# SWG_1_1.net
KiCad netlist of a schematic drawn in EAGLE
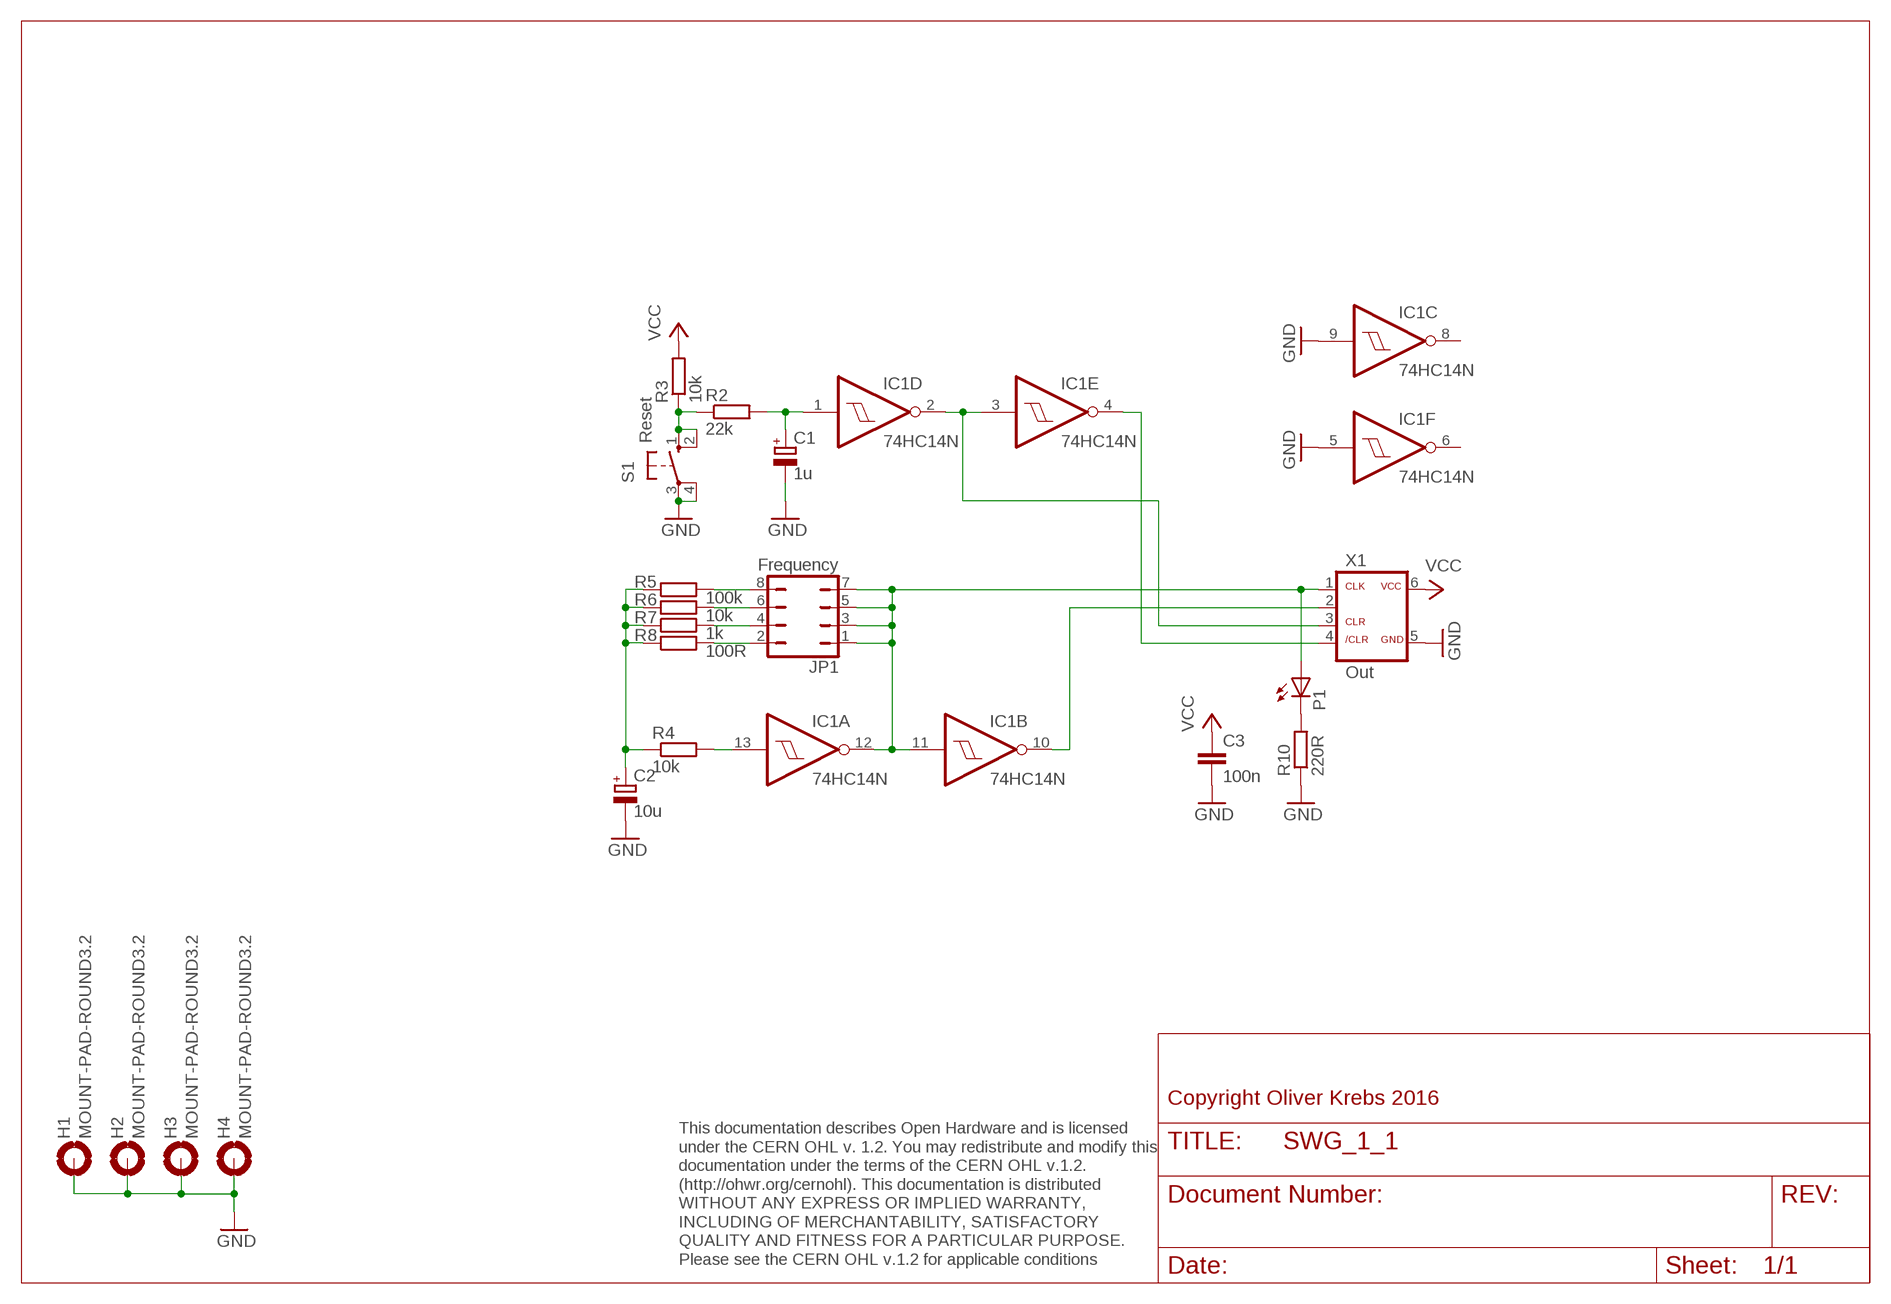
[diagram p0: schematic, sheet 1]

(export (version "E")
  (design (tool "Eeschema 10.0.6"))
  (components
    (comp (ref "C1")
      (value "1u")
      (footprint "eagle-import:E2-5")
      (libsource (lib "eagle-import") (part "CPOL-EUE2-5"))
    )
    (comp (ref "C2")
      (value "10u")
      (footprint "eagle-import:E2-5")
      (libsource (lib "eagle-import") (part "CPOL-EUE2-5"))
    )
    (comp (ref "C3")
      (value "100n")
      (footprint "eagle-import:C050-025X075")
      (libsource (lib "eagle-import") (part "C-EU050-025X075"))
    )
    (comp (ref "H1")
      (value "MOUNT-PAD-ROUND3.2")
      (footprint "eagle-import:3,2-PAD")
      (libsource (lib "eagle-import") (part "MOUNT-PAD-ROUND3.2"))
    )
    (comp (ref "H2")
      (value "MOUNT-PAD-ROUND3.2")
      (footprint "eagle-import:3,2-PAD")
      (libsource (lib "eagle-import") (part "MOUNT-PAD-ROUND3.2"))
    )
    (comp (ref "H3")
      (value "MOUNT-PAD-ROUND3.2")
      (footprint "eagle-import:3,2-PAD")
      (libsource (lib "eagle-import") (part "MOUNT-PAD-ROUND3.2"))
    )
    (comp (ref "H4")
      (value "MOUNT-PAD-ROUND3.2")
      (footprint "eagle-import:3,2-PAD")
      (libsource (lib "eagle-import") (part "MOUNT-PAD-ROUND3.2"))
    )
    (comp (ref "IC1")
      (value "74HC14N")
      (footprint "eagle-import:DIL14")
      (libsource (lib "eagle-import") (part "7414NHC"))
    )
    (comp (ref "JP1")
      (value "Frequency")
      (footprint "eagle-import:JP4Q")
      (libsource (lib "eagle-import") (part "JP4Q"))
    )
    (comp (ref "P1")
      (value "LED3MM")
      (footprint "eagle-import:LED3MM")
      (libsource (lib "eagle-import") (part "LED3MM"))
    )
    (comp (ref "R2")
      (value "22k")
      (footprint "eagle-import:0207_10")
      (libsource (lib "eagle-import") (part "R-EU_0207/10"))
    )
    (comp (ref "R3")
      (value "10k")
      (footprint "eagle-import:0207_10")
      (libsource (lib "eagle-import") (part "R-EU_0207/10"))
    )
    (comp (ref "R4")
      (value "10k")
      (footprint "eagle-import:0207_10")
      (libsource (lib "eagle-import") (part "R-EU_0207/10"))
    )
    (comp (ref "R5")
      (value "100k")
      (footprint "eagle-import:0207_10")
      (libsource (lib "eagle-import") (part "R-EU_0207/10"))
    )
    (comp (ref "R6")
      (value "10k")
      (footprint "eagle-import:0207_10")
      (libsource (lib "eagle-import") (part "R-EU_0207/10"))
    )
    (comp (ref "R7")
      (value "1k")
      (footprint "eagle-import:0207_10")
      (libsource (lib "eagle-import") (part "R-EU_0207/10"))
    )
    (comp (ref "R8")
      (value "100R")
      (footprint "eagle-import:0207_10")
      (libsource (lib "eagle-import") (part "R-EU_0207/10"))
    )
    (comp (ref "R10")
      (value "220R")
      (footprint "eagle-import:0207_10")
      (libsource (lib "eagle-import") (part "R-EU_0207/10"))
    )
    (comp (ref "S1")
      (value "Reset")
      (footprint "eagle-import:B3F-10XX")
      (fields (field (name "MPN") "B3F-1000"))
      (libsource (lib "eagle-import") (part "10-XX"))
    )
    (comp (ref "X1")
      (value "Out")
      (footprint "eagle-import:ML-6")
      (libsource (lib "eagle-import") (part "ML6C"))
    )
  )
  (nets
    (net (code "1") (name "GND") (class "Default")
      (node (ref "C1") (pin "-") (pinfunction "-_-") (pintype "passive"))
      (node (ref "C2") (pin "-") (pinfunction "-_-") (pintype "passive"))
      (node (ref "C3") (pin "2") (pinfunction "2_2") (pintype "passive"))
      (node (ref "H1") (pin "B3,2") (pinfunction "MOUNT_B3,2") (pintype "passive"))
      (node (ref "H2") (pin "B3,2") (pinfunction "MOUNT_B3,2") (pintype "passive"))
      (node (ref "H3") (pin "B3,2") (pinfunction "MOUNT_B3,2") (pintype "passive"))
      (node (ref "H4") (pin "B3,2") (pinfunction "MOUNT_B3,2") (pintype "passive"))
      (node (ref "IC1") (pin "5") (pinfunction "I_5") (pintype "input"))
      (node (ref "IC1") (pin "9") (pinfunction "I_9") (pintype "input"))
      (node (ref "R10") (pin "1") (pinfunction "1_1") (pintype "passive"))
      (node (ref "S1") (pin "3") (pinfunction "P_3") (pintype "passive"))
      (node (ref "S1") (pin "4") (pinfunction "P1_4") (pintype "passive"))
      (node (ref "X1") (pin "5") (pinfunction "5_5") (pintype "passive"))
    )
    (net (code "2") (name "Net-(C2-Pad+)") (class "Default")
      (node (ref "C2") (pin "+") (pinfunction "+_+") (pintype "passive"))
      (node (ref "R4") (pin "1") (pinfunction "1_1") (pintype "passive"))
      (node (ref "R5") (pin "1") (pinfunction "1_1") (pintype "passive"))
      (node (ref "R6") (pin "1") (pinfunction "1_1") (pintype "passive"))
      (node (ref "R7") (pin "1") (pinfunction "1_1") (pintype "passive"))
      (node (ref "R8") (pin "1") (pinfunction "1_1") (pintype "passive"))
    )
    (net (code "3") (name "Net-(IC1A-I)") (class "Default")
      (node (ref "IC1") (pin "13") (pinfunction "I_13") (pintype "input"))
      (node (ref "R4") (pin "2") (pinfunction "2_2") (pintype "passive"))
    )
    (net (code "4") (name "Net-(IC1A-O)") (class "Default")
      (node (ref "IC1") (pin "11") (pinfunction "I_11") (pintype "input"))
      (node (ref "IC1") (pin "12") (pinfunction "O_12") (pintype "output"))
      (node (ref "JP1") (pin "1") (pinfunction "1_1") (pintype "passive"))
      (node (ref "JP1") (pin "3") (pinfunction "3_3") (pintype "passive"))
      (node (ref "JP1") (pin "5") (pinfunction "5_5") (pintype "passive"))
      (node (ref "JP1") (pin "7") (pinfunction "7_7") (pintype "passive"))
      (node (ref "P1") (pin "A") (pinfunction "A_A") (pintype "passive"))
      (node (ref "X1") (pin "1") (pinfunction "1_1") (pintype "passive"))
    )
    (net (code "5") (name "Net-(IC1B-O)") (class "Default")
      (node (ref "IC1") (pin "10") (pinfunction "O_10") (pintype "output"))
      (node (ref "X1") (pin "2") (pinfunction "2_2") (pintype "passive"))
    )
    (net (code "6") (name "Net-(IC1D-I)") (class "Default")
      (node (ref "C1") (pin "+") (pinfunction "+_+") (pintype "passive"))
      (node (ref "IC1") (pin "1") (pinfunction "I_1") (pintype "input"))
      (node (ref "R2") (pin "2") (pinfunction "2_2") (pintype "passive"))
    )
    (net (code "7") (name "Net-(IC1D-O)") (class "Default")
      (node (ref "IC1") (pin "2") (pinfunction "O_2") (pintype "output"))
      (node (ref "IC1") (pin "3") (pinfunction "I_3") (pintype "input"))
      (node (ref "X1") (pin "3") (pinfunction "3_3") (pintype "passive"))
    )
    (net (code "8") (name "Net-(IC1E-O)") (class "Default")
      (node (ref "IC1") (pin "4") (pinfunction "O_4") (pintype "output"))
      (node (ref "X1") (pin "4") (pinfunction "4_4") (pintype "passive"))
    )
    (net (code "9") (name "Net-(JP1-Pad2)") (class "Default")
      (node (ref "JP1") (pin "2") (pinfunction "2_2") (pintype "passive"))
      (node (ref "R8") (pin "2") (pinfunction "2_2") (pintype "passive"))
    )
    (net (code "10") (name "Net-(JP1-Pad4)") (class "Default")
      (node (ref "JP1") (pin "4") (pinfunction "4_4") (pintype "passive"))
      (node (ref "R7") (pin "2") (pinfunction "2_2") (pintype "passive"))
    )
    (net (code "11") (name "Net-(JP1-Pad6)") (class "Default")
      (node (ref "JP1") (pin "6") (pinfunction "6_6") (pintype "passive"))
      (node (ref "R6") (pin "2") (pinfunction "2_2") (pintype "passive"))
    )
    (net (code "12") (name "Net-(JP1-Pad8)") (class "Default")
      (node (ref "JP1") (pin "8") (pinfunction "8_8") (pintype "passive"))
      (node (ref "R5") (pin "2") (pinfunction "2_2") (pintype "passive"))
    )
    (net (code "13") (name "Net-(P1-C)") (class "Default")
      (node (ref "P1") (pin "K") (pinfunction "C_K") (pintype "passive"))
      (node (ref "R10") (pin "2") (pinfunction "2_2") (pintype "passive"))
    )
    (net (code "14") (name "Net-(S1-S)") (class "Default")
      (node (ref "R2") (pin "1") (pinfunction "1_1") (pintype "passive"))
      (node (ref "R3") (pin "1") (pinfunction "1_1") (pintype "passive"))
      (node (ref "S1") (pin "1") (pinfunction "S_1") (pintype "passive"))
      (node (ref "S1") (pin "2") (pinfunction "S1_2") (pintype "passive"))
    )
    (net (code "15") (name "VCC") (class "Default")
      (node (ref "C3") (pin "1") (pinfunction "1_1") (pintype "passive"))
      (node (ref "R3") (pin "2") (pinfunction "2_2") (pintype "passive"))
      (node (ref "X1") (pin "6") (pinfunction "6_6") (pintype "passive"))
    )
    (net (code "16") (name "unconnected-(IC1C-O-Pad8)") (class "Default")
      (node (ref "IC1") (pin "8") (pinfunction "O_8") (pintype "output"))
    )
    (net (code "17") (name "unconnected-(IC1F-O-Pad6)") (class "Default")
      (node (ref "IC1") (pin "6") (pinfunction "O_6") (pintype "output"))
    )
  )
)
